# REF-IN-BLE-NS_4-2.net
KiCad netlist of a schematic drawn in EAGLE
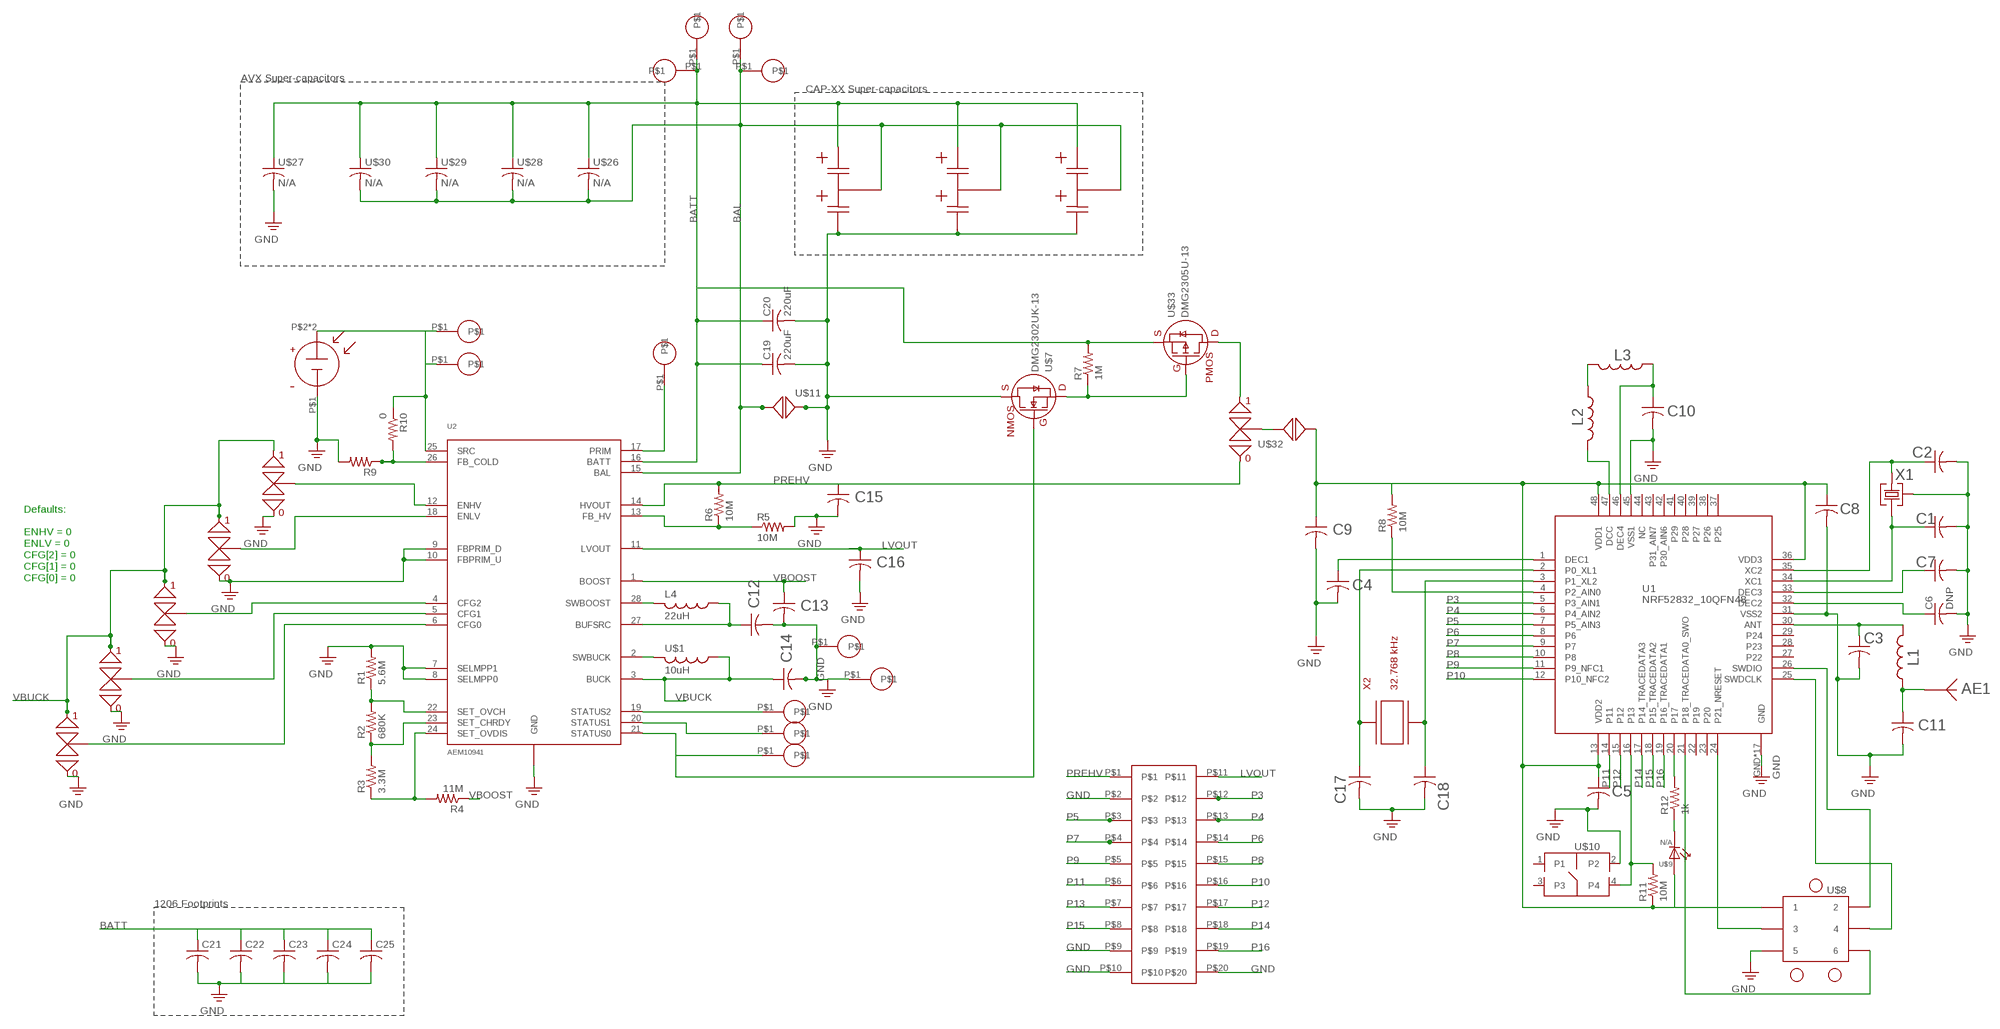
[diagram p0: schematic, sheet 1]

(export (version "E")
  (design (tool "Eeschema 10.0.6"))
  (components
    (comp (ref "AE1")
      (value "2.4GHZ_ANTENNAFLIPPED")
      (footprint "eagle-import:BLE_ANTENNA_NORDIC_FLIPPED")
      (libsource (lib "eagle-import") (part "2.4GHZ_ANTENNAFLIPPED"))
    )
    (comp (ref "C1")
      (value "12pF")
      (footprint "eagle-import:C0603")
      (fields (field (name "MFG_PART#") "C0603C120J5GACTU"))
      (libsource (lib "eagle-import") (part "C-USC0603T-12PF"))
    )
    (comp (ref "C2")
      (value "12pF")
      (footprint "eagle-import:C0603")
      (fields (field (name "MFG_PART#") "C0603C120J5GACTU"))
      (libsource (lib "eagle-import") (part "C-USC0603T-12PF"))
    )
    (comp (ref "C3")
      (value "0.8pF")
      (footprint "eagle-import:C0603")
      (fields (field (name "MFG_PART#") "CBR06C808B5GAC "))
      (libsource (lib "eagle-import") (part "C-USC0603T-0.8PF"))
    )
    (comp (ref "C4")
      (value "100nF")
      (footprint "eagle-import:C0603")
      (fields (field (name "MFG_PART#") "CL10B104KB8NNNC"))
      (libsource (lib "eagle-import") (part "C-USC0603T-100NF"))
    )
    (comp (ref "C5")
      (value "100nF")
      (footprint "eagle-import:C0603")
      (fields (field (name "MFG_PART#") "CL10B104KB8NNNC"))
      (libsource (lib "eagle-import") (part "C-USC0603T-100NF"))
    )
    (comp (ref "C6")
      (value "DNP")
      (footprint "eagle-import:C0603")
      (libsource (lib "eagle-import") (part "C-USC0603"))
    )
    (comp (ref "C7")
      (value "100pF")
      (footprint "eagle-import:C0603")
      (fields (field (name "MFG_PART#") "CL10C101JB8NNNC"))
      (libsource (lib "eagle-import") (part "C-USC0603T-100PF"))
    )
    (comp (ref "C8")
      (value "100nF")
      (footprint "eagle-import:C0603")
      (fields (field (name "MFG_PART#") "CL10B104KB8NNNC"))
      (libsource (lib "eagle-import") (part "C-USC0603T-100NF"))
    )
    (comp (ref "C9")
      (value "4.7uF")
      (footprint "eagle-import:C0603")
      (fields (field (name "MFG_PART#") "CL10A475KQ8NNWC "))
      (libsource (lib "eagle-import") (part "C-USC0603T-4.7UF"))
    )
    (comp (ref "C10")
      (value "1uF")
      (footprint "eagle-import:C0603")
      (fields (field (name "MFG_PART#") "CL10A105KP8NNNC ") (field (name "PERCENTAGE") "10%"))
      (libsource (lib "eagle-import") (part "C-USC0603T-1UF"))
    )
    (comp (ref "C11")
      (value "DNP")
      (footprint "eagle-import:C0603")
      (libsource (lib "eagle-import") (part "C-USC0603"))
    )
    (comp (ref "C12")
      (value "10uF")
      (footprint "eagle-import:C0603")
      (fields (field (name "MFG_PART#") "GRM188R61E106MA73D"))
      (libsource (lib "eagle-import") (part "C-USC0603T-10UF"))
    )
    (comp (ref "C13")
      (value "22uF")
      (footprint "eagle-import:C0603")
      (fields (field (name "MFG_PART#") "GRM188R61A226ME15D"))
      (libsource (lib "eagle-import") (part "C-USC0603T-22UF"))
    )
    (comp (ref "C14")
      (value "10uF")
      (footprint "eagle-import:C0603")
      (fields (field (name "MFG_PART#") "GRM188R61E106MA73D"))
      (libsource (lib "eagle-import") (part "C-USC0603T-10UF"))
    )
    (comp (ref "C15")
      (value "10uF")
      (footprint "eagle-import:C0603")
      (fields (field (name "MFG_PART#") "GRM188R61E106MA73D"))
      (libsource (lib "eagle-import") (part "C-USC0603T-10UF"))
    )
    (comp (ref "C16")
      (value "10uF")
      (footprint "eagle-import:C0603")
      (fields (field (name "MFG_PART#") "GRM188R61E106MA73D"))
      (libsource (lib "eagle-import") (part "C-USC0603T-10UF"))
    )
    (comp (ref "C17")
      (value "12pF")
      (footprint "eagle-import:C0603")
      (fields (field (name "MFG_PART#") "C0603C120J5GACTU"))
      (libsource (lib "eagle-import") (part "C-USC0603T-12PF"))
    )
    (comp (ref "C18")
      (value "12pF")
      (footprint "eagle-import:C0603")
      (fields (field (name "MFG_PART#") "C0603C120J5GACTU"))
      (libsource (lib "eagle-import") (part "C-USC0603T-12PF"))
    )
    (comp (ref "C19")
      (value "220uF")
      (footprint "eagle-import:C1206")
      (fields (field (name "MFG_PART#") "GRM31CC80G227ME11L"))
      (libsource (lib "eagle-import") (part "C-USC1206T-220UF"))
    )
    (comp (ref "C20")
      (value "220uF")
      (footprint "eagle-import:C1206")
      (fields (field (name "MFG_PART#") "GRM31CC80G227ME11L"))
      (libsource (lib "eagle-import") (part "C-USC1206T-220UF"))
    )
    (comp (ref "C21")
      (value "C-USC1206")
      (footprint "eagle-import:C1206")
      (libsource (lib "eagle-import") (part "C-USC1206"))
    )
    (comp (ref "C22")
      (value "C-USC1206")
      (footprint "eagle-import:C1206")
      (libsource (lib "eagle-import") (part "C-USC1206"))
    )
    (comp (ref "C23")
      (value "C-USC1206")
      (footprint "eagle-import:C1206")
      (libsource (lib "eagle-import") (part "C-USC1206"))
    )
    (comp (ref "C24")
      (value "C-USC1206")
      (footprint "eagle-import:C1206")
      (libsource (lib "eagle-import") (part "C-USC1206"))
    )
    (comp (ref "C25")
      (value "C-USC1206")
      (footprint "eagle-import:C1206")
      (libsource (lib "eagle-import") (part "C-USC1206"))
    )
    (comp (ref "L1")
      (value "3.9nH")
      (footprint "eagle-import:L0603")
      (fields (field (name "MFG_PART#") "L-14C3N9SV4T "))
      (libsource (lib "eagle-import") (part "L0603V-3.9NH"))
    )
    (comp (ref "L2")
      (value "10uH")
      (footprint "eagle-import:L0603")
      (fields (field (name "MFG_PART#") "LBR2012T100M"))
      (libsource (lib "eagle-import") (part "L0603V-10UH"))
    )
    (comp (ref "L3")
      (value "15nH")
      (footprint "eagle-import:L0603")
      (fields (field (name "MFG_PART#") "L-14C15NJV4T"))
      (libsource (lib "eagle-import") (part "L0603V-15NH"))
    )
    (comp (ref "L4")
      (value "22uH")
      (footprint "eagle-import:744031220")
      (fields (field (name "MFG_PART#") "744031220"))
      (libsource (lib "eagle-import") (part "744031220"))
    )
    (comp (ref "R1")
      (value "5.6M")
      (footprint "eagle-import:R0603")
      (libsource (lib "eagle-import") (part "R-US_R0603"))
    )
    (comp (ref "R2")
      (value "680K")
      (footprint "eagle-import:R0603")
      (libsource (lib "eagle-import") (part "R-US_R0603"))
    )
    (comp (ref "R3")
      (value "3.3M")
      (footprint "eagle-import:R0603")
      (libsource (lib "eagle-import") (part "R-US_R0603"))
    )
    (comp (ref "R4")
      (value "11M")
      (footprint "eagle-import:R0603")
      (libsource (lib "eagle-import") (part "R-US_R0603"))
    )
    (comp (ref "R5")
      (value "10M")
      (footprint "eagle-import:R0603")
      (libsource (lib "eagle-import") (part "R-US_R0603"))
    )
    (comp (ref "R6")
      (value "10M")
      (footprint "eagle-import:R0603")
      (libsource (lib "eagle-import") (part "R-US_R0603"))
    )
    (comp (ref "R7")
      (value "1M")
      (footprint "eagle-import:R0603")
      (libsource (lib "eagle-import") (part "R-US_R0603"))
    )
    (comp (ref "R8")
      (value "10M")
      (footprint "eagle-import:R0603")
      (libsource (lib "eagle-import") (part "R-US_R0603"))
    )
    (comp (ref "R9")
      (value "R-US_R0603")
      (footprint "eagle-import:R0603")
      (libsource (lib "eagle-import") (part "R-US_R0603"))
    )
    (comp (ref "R10")
      (value "0")
      (footprint "eagle-import:R0603")
      (libsource (lib "eagle-import") (part "R-US_R0603"))
    )
    (comp (ref "R11")
      (value "10M")
      (footprint "eagle-import:R0603")
      (libsource (lib "eagle-import") (part "R-US_R0603"))
    )
    (comp (ref "R12")
      (value "1k")
      (footprint "eagle-import:R0603")
      (libsource (lib "eagle-import") (part "R-US_R0603"))
    )
    (comp (ref "U$1")
      (value "10uH")
      (footprint "eagle-import:L0603")
      (fields (field (name "MFG_PART#") "LBR2012T100M"))
      (libsource (lib "eagle-import") (part "L0603V-10UH"))
    )
    (comp (ref "U$2")
      (value "N/A")
      (footprint "eagle-import:DOUBLE_SOLDER_BRIDGE_0_CLOSED")
      (libsource (lib "eagle-import") (part "DOUBLE_SOLDER_BRIDGE0_CLOSED"))
    )
    (comp (ref "U$3")
      (value "N/A")
      (footprint "eagle-import:DOUBLE_SOLDER_BRIDGE_0_CLOSED")
      (libsource (lib "eagle-import") (part "DOUBLE_SOLDER_BRIDGE0_CLOSED"))
    )
    (comp (ref "U$4")
      (value "N/A")
      (footprint "eagle-import:DOUBLE_SOLDER_BRIDGE_0_CLOSED")
      (libsource (lib "eagle-import") (part "DOUBLE_SOLDER_BRIDGE0_CLOSED"))
    )
    (comp (ref "U$5")
      (value "N/A")
      (footprint "eagle-import:DOUBLE_SOLDER_BRIDGE_0_CLOSED")
      (libsource (lib "eagle-import") (part "DOUBLE_SOLDER_BRIDGE0_CLOSED"))
    )
    (comp (ref "U$6")
      (value "N/A")
      (footprint "eagle-import:DOUBLE_SOLDER_BRIDGE_0_CLOSED")
      (libsource (lib "eagle-import") (part "DOUBLE_SOLDER_BRIDGE0_CLOSED"))
    )
    (comp (ref "U$7")
      (value "DMG2302UK-13")
      (footprint "eagle-import:SOT-23-3-DIODESINC")
      (libsource (lib "eagle-import") (part "DMG2302UK-13"))
    )
    (comp (ref "U$8")
      (value "N/A")
      (footprint "eagle-import:TC2030-IDC")
      (libsource (lib "eagle-import") (part "TC2030-IDC"))
    )
    (comp (ref "U$9")
      (value "N/A")
      (footprint "eagle-import:APT1608LZGCK")
      (fields (field (name "MFG_PART#") "APT1608LZGCK"))
      (libsource (lib "eagle-import") (part "APT1608LZGCK"))
    )
    (comp (ref "U$10")
      (value "MJTP1140")
      (footprint "eagle-import:MJTP1140A")
      (fields (field (name "MFG_PART#") "TL3315NF100Q "))
      (libsource (lib "eagle-import") (part "MJTP1140"))
    )
    (comp (ref "U$11")
      (value "SOLDER_BRIGDECLOSED")
      (footprint "eagle-import:SOLDER_BRIDGE_CLOSED")
      (libsource (lib "eagle-import") (part "SOLDER_BRIGDECLOSED"))
    )
    (comp (ref "U$12")
      (value "N/A")
      (footprint "eagle-import:1MM_PAD")
      (libsource (lib "eagle-import") (part "1MM_PAD"))
    )
    (comp (ref "U$13")
      (value "N/A")
      (footprint "eagle-import:1MM_PAD")
      (libsource (lib "eagle-import") (part "1MM_PAD"))
    )
    (comp (ref "U$14")
      (value "N/A")
      (footprint "eagle-import:1MM_PAD")
      (libsource (lib "eagle-import") (part "1MM_PAD"))
    )
    (comp (ref "U$15")
      (value "N/A")
      (footprint "eagle-import:1MM_PAD")
      (libsource (lib "eagle-import") (part "1MM_PAD"))
    )
    (comp (ref "U$16")
      (value "N/A")
      (footprint "eagle-import:SOLAR_CELL_37X54MM")
      (libsource (lib "eagle-import") (part "SOLAR_CELL_LL200_2.4_37"))
    )
    (comp (ref "U$17")
      (value "N/A")
      (footprint "eagle-import:1MM_PAD")
      (libsource (lib "eagle-import") (part "1MM_PAD"))
    )
    (comp (ref "U$18")
      (value "N/A")
      (footprint "eagle-import:1MM_PAD")
      (libsource (lib "eagle-import") (part "1MM_PAD"))
    )
    (comp (ref "U$19")
      (value "N/A")
      (footprint "eagle-import:1MM_PAD")
      (libsource (lib "eagle-import") (part "1MM_PAD"))
    )
    (comp (ref "U$20")
      (value "20PIN_CONN")
      (footprint "eagle-import:20PIN_CONN")
      (libsource (lib "eagle-import") (part "20PIN_CONN"))
    )
    (comp (ref "U$23")
      (value "N/A")
      (footprint "eagle-import:CAP-XX_A-TYPE")
      (libsource (lib "eagle-import") (part "CAP-XX_A-TYPE"))
    )
    (comp (ref "U$24")
      (value "N/A")
      (footprint "eagle-import:CAP-XX_S-TYPE")
      (libsource (lib "eagle-import") (part "CAP-XX_S-TYPE"))
    )
    (comp (ref "U$25")
      (value "N/A")
      (footprint "eagle-import:CAP-XX_W-TYPE")
      (libsource (lib "eagle-import") (part "CAP-XX_W-TYPE"))
    )
    (comp (ref "U$26")
      (value "N/A")
      (footprint "eagle-import:BZ01_L-TYPE")
      (libsource (lib "eagle-import") (part "BZ01_L-TYPE"))
    )
    (comp (ref "U$27")
      (value "N/A")
      (footprint "eagle-import:BZ059_N-TYPE")
      (libsource (lib "eagle-import") (part "BZ059_N-TYPE"))
    )
    (comp (ref "U$28")
      (value "N/A")
      (footprint "eagle-import:BZ01_S-TYPE")
      (libsource (lib "eagle-import") (part "BZ01_S-TYPE"))
    )
    (comp (ref "U$29")
      (value "N/A")
      (footprint "eagle-import:BZ05_S-TYPE")
      (libsource (lib "eagle-import") (part "BZ05_S-TYPE"))
    )
    (comp (ref "U$30")
      (value "N/A")
      (footprint "eagle-import:BZ09_S-TYPE")
      (libsource (lib "eagle-import") (part "BZ09_S-TYPE"))
    )
    (comp (ref "U$31")
      (value "DOUBLE_SOLDER_BRIDGE1_CLOSED")
      (footprint "eagle-import:DOUBLE_SOLDER_BRIDGE_1_CLOSED")
      (libsource (lib "eagle-import") (part "DOUBLE_SOLDER_BRIDGE1_CLOSED"))
    )
    (comp (ref "U$32")
      (value "SOLDER_BRIGDECLOSED")
      (footprint "eagle-import:SOLDER_BRIDGE_CLOSED")
      (libsource (lib "eagle-import") (part "SOLDER_BRIGDECLOSED"))
    )
    (comp (ref "U$33")
      (value "DMG2305U-13")
      (footprint "eagle-import:SOT-23-3-DIODESINC")
      (libsource (lib "eagle-import") (part "DMG2305U-13"))
    )
    (comp (ref "U$35")
      (value "N/A")
      (footprint "eagle-import:1MM_PAD")
      (libsource (lib "eagle-import") (part "1MM_PAD"))
    )
    (comp (ref "U$36")
      (value "N/A")
      (footprint "eagle-import:1MM_PAD")
      (libsource (lib "eagle-import") (part "1MM_PAD"))
    )
    (comp (ref "U$39")
      (value "N/A")
      (footprint "eagle-import:1MM_PAD")
      (libsource (lib "eagle-import") (part "1MM_PAD"))
    )
    (comp (ref "U$40")
      (value "N/A")
      (footprint "eagle-import:1MM_PAD")
      (libsource (lib "eagle-import") (part "1MM_PAD"))
    )
    (comp (ref "U$41")
      (value "N/A")
      (footprint "eagle-import:1MM_PAD")
      (libsource (lib "eagle-import") (part "1MM_PAD"))
    )
    (comp (ref "U1")
      (value "NRF52832_10QFN48")
      (footprint "eagle-import:NRF52832_10")
      (fields (field (name "MFG_PART#") "NRF52832-QFAA-R"))
      (libsource (lib "eagle-import") (part "NRF52832_10QFN48"))
    )
    (comp (ref "U2")
      (value "AEM10941")
      (footprint "eagle-import:QFN28_5X5_05PITCH")
      (fields (field (name "MFG_PART#") "AEM10941-QFN "))
      (libsource (lib "eagle-import") (part "AEM10941"))
    )
    (comp (ref "X1")
      (value "32 MHz")
      (footprint "eagle-import:FA-128-EPSON")
      (fields (field (name "MFG_PART#") "FA-128 32.0000MF10Z-AJ3"))
      (libsource (lib "eagle-import") (part "FA-128-32MHZMF10Z-AJ5"))
    )
    (comp (ref "X2")
      (value "32.768 kHz")
      (footprint "eagle-import:FC-135")
      (fields (field (name "MFG_PART#") "FC-135 32.7680KA-AC"))
      (libsource (lib "eagle-import") (part "FC-135_32.7680KA-AC"))
    )
  )
  (nets
    (net (code "1") (name "/BAL") (class "Default")
      (node (ref "U$11") (pin "P$1") (pinfunction "P1_P$1") (pintype "bidirectional"))
      (node (ref "U$19") (pin "P$1") (pinfunction "P$1_P$1") (pintype "bidirectional"))
      (node (ref "U$23") (pin "P$1") (pinfunction "BAL_P$1") (pintype "bidirectional"))
      (node (ref "U$24") (pin "P$1") (pinfunction "BAL_P$1") (pintype "bidirectional"))
      (node (ref "U$25") (pin "P$1") (pinfunction "BAL_P$1") (pintype "bidirectional"))
      (node (ref "U$26") (pin "P$3") (pinfunction "2_P$3") (pintype "passive"))
      (node (ref "U$26") (pin "P$4") (pinfunction "2_P$4") (pintype "passive"))
      (node (ref "U$28") (pin "P$3") (pinfunction "2_P$3") (pintype "passive"))
      (node (ref "U$29") (pin "P$3") (pinfunction "2_P$3") (pintype "passive"))
      (node (ref "U$30") (pin "P$3") (pinfunction "2_P$3") (pintype "passive"))
      (node (ref "U$41") (pin "P$1") (pinfunction "P$1_P$1") (pintype "bidirectional"))
      (node (ref "U2") (pin "15") (pinfunction "BAL_15") (pintype "bidirectional"))
    )
    (net (code "2") (name "/BATT") (class "Default")
      (node (ref "C19") (pin "1") (pinfunction "1_1") (pintype "passive"))
      (node (ref "C20") (pin "1") (pinfunction "1_1") (pintype "passive"))
      (node (ref "C21") (pin "1") (pinfunction "1_1") (pintype "passive"))
      (node (ref "C22") (pin "1") (pinfunction "1_1") (pintype "passive"))
      (node (ref "C23") (pin "1") (pinfunction "1_1") (pintype "passive"))
      (node (ref "C24") (pin "1") (pinfunction "1_1") (pintype "passive"))
      (node (ref "C25") (pin "1") (pinfunction "1_1") (pintype "passive"))
      (node (ref "R7") (pin "2") (pinfunction "2_2") (pintype "passive"))
      (node (ref "U$18") (pin "P$1") (pinfunction "P$1_P$1") (pintype "bidirectional"))
      (node (ref "U$23") (pin "P$2") (pinfunction "+_P$2") (pintype "bidirectional"))
      (node (ref "U$24") (pin "P$2") (pinfunction "+_P$2") (pintype "bidirectional"))
      (node (ref "U$25") (pin "P$2") (pinfunction "+_P$2") (pintype "bidirectional"))
      (node (ref "U$26") (pin "P$1") (pinfunction "1_P$1") (pintype "passive"))
      (node (ref "U$26") (pin "P$2") (pinfunction "1_P$2") (pintype "passive"))
      (node (ref "U$27") (pin "P$1") (pinfunction "1_P$1") (pintype "passive"))
      (node (ref "U$28") (pin "P$1") (pinfunction "1_P$1") (pintype "passive"))
      (node (ref "U$28") (pin "P$2") (pinfunction "1_P$2") (pintype "passive"))
      (node (ref "U$29") (pin "P$1") (pinfunction "1_P$1") (pintype "passive"))
      (node (ref "U$29") (pin "P$2") (pinfunction "1_P$2") (pintype "passive"))
      (node (ref "U$30") (pin "P$1") (pinfunction "1_P$1") (pintype "passive"))
      (node (ref "U$30") (pin "P$2") (pinfunction "1_P$2") (pintype "passive"))
      (node (ref "U$33") (pin "2") (pinfunction "S_2") (pintype "bidirectional"))
      (node (ref "U$40") (pin "P$1") (pinfunction "P$1_P$1") (pintype "bidirectional"))
      (node (ref "U2") (pin "16") (pinfunction "BATT_16") (pintype "bidirectional"))
    )
    (net (code "3") (name "/LVOUT") (class "Default")
      (node (ref "C16") (pin "1") (pinfunction "1_1") (pintype "passive"))
      (node (ref "U$20") (pin "P$11") (pinfunction "P$11_P$11") (pintype "bidirectional"))
      (node (ref "U2") (pin "11") (pinfunction "LVOUT_11") (pintype "output"))
    )
    (net (code "4") (name "/P3") (class "Default")
      (node (ref "U$20") (pin "P$12") (pinfunction "P$12_P$12") (pintype "bidirectional"))
      (node (ref "U1") (pin "5") (pinfunction "P3_AIN1_5") (pintype "bidirectional"))
    )
    (net (code "5") (name "/P4") (class "Default")
      (node (ref "U$20") (pin "P$13") (pinfunction "P$13_P$13") (pintype "bidirectional"))
      (node (ref "U1") (pin "6") (pinfunction "P4_AIN2_6") (pintype "bidirectional"))
    )
    (net (code "6") (name "/P5") (class "Default")
      (node (ref "U$20") (pin "P$3") (pinfunction "P$3_P$3") (pintype "bidirectional"))
      (node (ref "U1") (pin "7") (pinfunction "P5_AIN3_7") (pintype "bidirectional"))
    )
    (net (code "7") (name "/P6") (class "Default")
      (node (ref "U$20") (pin "P$14") (pinfunction "P$14_P$14") (pintype "bidirectional"))
      (node (ref "U1") (pin "8") (pinfunction "P6_8") (pintype "bidirectional"))
    )
    (net (code "8") (name "/P7") (class "Default")
      (node (ref "U$20") (pin "P$4") (pinfunction "P$4_P$4") (pintype "bidirectional"))
      (node (ref "U1") (pin "9") (pinfunction "P7_9") (pintype "bidirectional"))
    )
    (net (code "9") (name "/P8") (class "Default")
      (node (ref "U$20") (pin "P$15") (pinfunction "P$15_P$15") (pintype "bidirectional"))
      (node (ref "U1") (pin "10") (pinfunction "P8_10") (pintype "bidirectional"))
    )
    (net (code "10") (name "/P9") (class "Default")
      (node (ref "U$20") (pin "P$5") (pinfunction "P$5_P$5") (pintype "bidirectional"))
      (node (ref "U1") (pin "11") (pinfunction "P9_NFC1_11") (pintype "bidirectional"))
    )
    (net (code "11") (name "/P10") (class "Default")
      (node (ref "U$20") (pin "P$16") (pinfunction "P$16_P$16") (pintype "bidirectional"))
      (node (ref "U1") (pin "12") (pinfunction "P10_NFC2_12") (pintype "bidirectional"))
    )
    (net (code "12") (name "/P11") (class "Default")
      (node (ref "U$20") (pin "P$6") (pinfunction "P$6_P$6") (pintype "bidirectional"))
      (node (ref "U1") (pin "14") (pinfunction "P11_14") (pintype "bidirectional"))
    )
    (net (code "13") (name "/P12") (class "Default")
      (node (ref "U$20") (pin "P$17") (pinfunction "P$17_P$17") (pintype "bidirectional"))
      (node (ref "U1") (pin "15") (pinfunction "P12_15") (pintype "bidirectional"))
    )
    (net (code "14") (name "/P13") (class "Default")
      (node (ref "U$20") (pin "P$7") (pinfunction "P$7_P$7") (pintype "bidirectional"))
    )
    (net (code "15") (name "/P14") (class "Default")
      (node (ref "U$20") (pin "P$18") (pinfunction "P$18_P$18") (pintype "bidirectional"))
      (node (ref "U1") (pin "17") (pinfunction "P14_TRACEDATA3_17") (pintype "bidirectional"))
    )
    (net (code "16") (name "/P15") (class "Default")
      (node (ref "U$20") (pin "P$8") (pinfunction "P$8_P$8") (pintype "bidirectional"))
      (node (ref "U1") (pin "18") (pinfunction "P15_TRACEDATA2_18") (pintype "bidirectional"))
    )
    (net (code "17") (name "/P16") (class "Default")
      (node (ref "U$20") (pin "P$19") (pinfunction "P$19_P$19") (pintype "bidirectional"))
      (node (ref "U1") (pin "19") (pinfunction "P16_TRACEDATA1_19") (pintype "bidirectional"))
    )
    (net (code "18") (name "/PREHV") (class "Default")
      (node (ref "C15") (pin "1") (pinfunction "1_1") (pintype "passive"))
      (node (ref "R6") (pin "2") (pinfunction "2_2") (pintype "passive"))
      (node (ref "U$20") (pin "P$1") (pinfunction "P$1_P$1") (pintype "bidirectional"))
      (node (ref "U$31") (pin "IN0") (pinfunction "IN0_IN0") (pintype "bidirectional"))
      (node (ref "U2") (pin "14") (pinfunction "HVOUT_14") (pintype "output"))
    )
    (net (code "19") (name "/VBOOST") (class "Default")
      (node (ref "C13") (pin "1") (pinfunction "1_1") (pintype "passive"))
      (node (ref "R4") (pin "1") (pinfunction "1_1") (pintype "passive"))
      (node (ref "U2") (pin "1") (pinfunction "BOOST_1") (pintype "bidirectional"))
    )
    (net (code "20") (name "/VBUCK") (class "Default")
      (node (ref "C14") (pin "1") (pinfunction "1_1") (pintype "passive"))
      (node (ref "U$1") (pin "1") (pinfunction "1_1") (pintype "passive"))
      (node (ref "U$2") (pin "IN1") (pinfunction "IN1_IN1") (pintype "bidirectional"))
      (node (ref "U$3") (pin "IN1") (pinfunction "IN1_IN1") (pintype "bidirectional"))
      (node (ref "U$4") (pin "IN1") (pinfunction "IN1_IN1") (pintype "bidirectional"))
      (node (ref "U$5") (pin "IN1") (pinfunction "IN1_IN1") (pintype "bidirectional"))
      (node (ref "U$6") (pin "IN1") (pinfunction "IN1_IN1") (pintype "bidirectional"))
      (node (ref "U2") (pin "3") (pinfunction "BUCK_3") (pintype "bidirectional"))
    )
    (net (code "21") (name "GND") (class "Default")
      (node (ref "C1") (pin "2") (pinfunction "2_2") (pintype "passive"))
      (node (ref "C10") (pin "2") (pinfunction "2_2") (pintype "passive"))
      (node (ref "C11") (pin "2") (pinfunction "2_2") (pintype "passive"))
      (node (ref "C12") (pin "2") (pinfunction "2_2") (pintype "passive"))
      (node (ref "C13") (pin "2") (pinfunction "2_2") (pintype "passive"))
      (node (ref "C14") (pin "2") (pinfunction "2_2") (pintype "passive"))
      (node (ref "C15") (pin "2") (pinfunction "2_2") (pintype "passive"))
      (node (ref "C16") (pin "2") (pinfunction "2_2") (pintype "passive"))
      (node (ref "C17") (pin "2") (pinfunction "2_2") (pintype "passive"))
      (node (ref "C18") (pin "2") (pinfunction "2_2") (pintype "passive"))
      (node (ref "C19") (pin "2") (pinfunction "2_2") (pintype "passive"))
      (node (ref "C2") (pin "2") (pinfunction "2_2") (pintype "passive"))
      (node (ref "C20") (pin "2") (pinfunction "2_2") (pintype "passive"))
      (node (ref "C21") (pin "2") (pinfunction "2_2") (pintype "passive"))
      (node (ref "C22") (pin "2") (pinfunction "2_2") (pintype "passive"))
      (node (ref "C23") (pin "2") (pinfunction "2_2") (pintype "passive"))
      (node (ref "C24") (pin "2") (pinfunction "2_2") (pintype "passive"))
      (node (ref "C25") (pin "2") (pinfunction "2_2") (pintype "passive"))
      (node (ref "C3") (pin "2") (pinfunction "2_2") (pintype "passive"))
      (node (ref "C4") (pin "2") (pinfunction "2_2") (pintype "passive"))
      (node (ref "C5") (pin "2") (pinfunction "2_2") (pintype "passive"))
      (node (ref "C6") (pin "2") (pinfunction "2_2") (pintype "passive"))
      (node (ref "C7") (pin "2") (pinfunction "2_2") (pintype "passive"))
      (node (ref "C8") (pin "2") (pinfunction "2_2") (pintype "passive"))
      (node (ref "C9") (pin "2") (pinfunction "2_2") (pintype "passive"))
      (node (ref "R1") (pin "2") (pinfunction "2_2") (pintype "passive"))
      (node (ref "R5") (pin "2") (pinfunction "2_2") (pintype "passive"))
      (node (ref "R9") (pin "2") (pinfunction "2_2") (pintype "passive"))
      (node (ref "U$10") (pin "2") (pinfunction "P2_2") (pintype "bidirectional"))
      (node (ref "U$11") (pin "P$2") (pinfunction "P2_P$2") (pintype "bidirectional"))
      (node (ref "U$16") (pin "P$1") (pinfunction "GND_P$1") (pintype "bidirectional"))
      (node (ref "U$17") (pin "P$1") (pinfunction "P$1_P$1") (pintype "bidirectional"))
      (node (ref "U$2") (pin "IN0") (pinfunction "IN0_IN0") (pintype "bidirectional"))
      (node (ref "U$20") (pin "P$10") (pinfunction "P$10_P$10") (pintype "bidirectional"))
      (node (ref "U$20") (pin "P$2") (pinfunction "P$2_P$2") (pintype "bidirectional"))
      (node (ref "U$20") (pin "P$20") (pinfunction "P$20_P$20") (pintype "bidirectional"))
      (node (ref "U$20") (pin "P$9") (pinfunction "P$9_P$9") (pintype "bidirectional"))
      (node (ref "U$23") (pin "P$3") (pinfunction "-_P$3") (pintype "bidirectional"))
      (node (ref "U$24") (pin "P$3") (pinfunction "-_P$3") (pintype "bidirectional"))
      (node (ref "U$25") (pin "P$3") (pinfunction "-_P$3") (pintype "bidirectional"))
      (node (ref "U$27") (pin "P$2") (pinfunction "2_P$2") (pintype "passive"))
      (node (ref "U$3") (pin "IN0") (pinfunction "IN0_IN0") (pintype "bidirectional"))
      (node (ref "U$35") (pin "P$1") (pinfunction "P$1_P$1") (pintype "bidirectional"))
      (node (ref "U$4") (pin "IN0") (pinfunction "IN0_IN0") (pintype "bidirectional"))
      (node (ref "U$5") (pin "IN0") (pinfunction "IN0_IN0") (pintype "bidirectional"))
      (node (ref "U$6") (pin "IN0") (pinfunction "IN0_IN0") (pintype "bidirectional"))
      (node (ref "U$7") (pin "2") (pinfunction "S_2") (pintype "bidirectional"))
      (node (ref "U$8") (pin "P5") (pinfunction "5_P5") (pintype "bidirectional"))
      (node (ref "U1") (pin "31") (pinfunction "VSS2_31") (pintype "bidirectional"))
      (node (ref "U1") (pin "45") (pinfunction "VSS1_45") (pintype "bidirectional"))
      (node (ref "U1") (pin "GND") (pinfunction "GND_GND") (pintype "bidirectional"))
      (node (ref "U1") (pin "P$10") (pinfunction "GND_P$10") (pintype "bidirectional"))
      (node (ref "U1") (pin "P$11") (pinfunction "GND_P$11") (pintype "bidirectional"))
      (node (ref "U1") (pin "P$12") (pinfunction "GND_P$12") (pintype "bidirectional"))
      (node (ref "U1") (pin "P$13") (pinfunction "GND_P$13") (pintype "bidirectional"))
      (node (ref "U1") (pin "P$14") (pinfunction "GND_P$14") (pintype "bidirectional"))
      (node (ref "U1") (pin "P$15") (pinfunction "GND_P$15") (pintype "bidirectional"))
      (node (ref "U1") (pin "P$16") (pinfunction "GND_P$16") (pintype "bidirectional"))
      (node (ref "U1") (pin "P$17") (pinfunction "GND_P$17") (pintype "bidirectional"))
      (node (ref "U1") (pin "P$2") (pinfunction "GND_P$2") (pintype "bidirectional"))
      (node (ref "U1") (pin "P$3") (pinfunction "GND_P$3") (pintype "bidirectional"))
      (node (ref "U1") (pin "P$4") (pinfunction "GND_P$4") (pintype "bidirectional"))
      (node (ref "U1") (pin "P$5") (pinfunction "GND_P$5") (pintype "bidirectional"))
      (node (ref "U1") (pin "P$6") (pinfunction "GND_P$6") (pintype "bidirectional"))
      (node (ref "U1") (pin "P$7") (pinfunction "GND_P$7") (pintype "bidirectional"))
      (node (ref "U1") (pin "P$8") (pinfunction "GND_P$8") (pintype "bidirectional"))
      (node (ref "U1") (pin "P$9") (pinfunction "GND_P$9") (pintype "bidirectional"))
      (node (ref "U2") (pin "10") (pinfunction "FBPRIM_U_10") (pintype "bidirectional"))
      (node (ref "U2") (pin "7") (pinfunction "SELMPP1_7") (pintype "input"))
      (node (ref "U2") (pin "8") (pinfunction "SELMPP0_8") (pintype "input"))
      (node (ref "U2") (pin "9") (pinfunction "FBPRIM_D_9") (pintype "bidirectional"))
      (node (ref "U2") (pin "GND") (pinfunction "GND_GND") (pintype "power_in"))
      (node (ref "U2") (pin "GND1") (pinfunction "GND_GND1") (pintype "power_in"))
      (node (ref "U2") (pin "GND2") (pinfunction "GND_GND2") (pintype "power_in"))
      (node (ref "U2") (pin "GND3") (pinfunction "GND_GND3") (pintype "power_in"))
      (node (ref "U2") (pin "GND4") (pinfunction "GND_GND4") (pintype "power_in"))
      (node (ref "U2") (pin "GND5") (pinfunction "GND_GND5") (pintype "power_in"))
      (node (ref "X1") (pin "P2") (pinfunction "P3_P2") (pintype "bidirectional"))
      (node (ref "X1") (pin "P4") (pinfunction "P3_P4") (pintype "bidirectional"))
    )
    (net (code "22") (name "Net-(AE1-PadP$1)") (class "Default")
      (node (ref "AE1") (pin "P$1") (pinfunction "P$1_P$1") (pintype "bidirectional"))
      (node (ref "C11") (pin "1") (pinfunction "1_1") (pintype "passive"))
      (node (ref "L1") (pin "1") (pinfunction "1_1") (pintype "passive"))
    )
    (net (code "23") (name "Net-(L2-Pad1)") (class "Default")
      (node (ref "L2") (pin "1") (pinfunction "1_1") (pintype "passive"))
      (node (ref "L3") (pin "2") (pinfunction "2_2") (pintype "passive"))
    )
    (net (code "24") (name "Net-(L4-1)") (class "Default")
      (node (ref "C12") (pin "1") (pinfunction "1_1") (pintype "passive"))
      (node (ref "L4") (pin "PIN1") (pinfunction "1_PIN1") (pintype "passive"))
      (node (ref "U2") (pin "27") (pinfunction "BUFSRC_27") (pintype "bidirectional"))
    )
    (net (code "25") (name "Net-(L4-2)") (class "Default")
      (node (ref "L4") (pin "PIN2") (pinfunction "2_PIN2") (pintype "passive"))
      (node (ref "U2") (pin "28") (pinfunction "SWBOOST_28") (pintype "bidirectional"))
    )
    (net (code "26") (name "Net-(R12-Pad1)") (class "Default")
      (node (ref "R12") (pin "1") (pinfunction "1_1") (pintype "passive"))
      (node (ref "U$9") (pin "C") (pinfunction "C_C") (pintype "bidirectional"))
    )
    (net (code "27") (name "Net-(U$7-G)") (class "Default")
      (node (ref "U$15") (pin "P$1") (pinfunction "P$1_P$1") (pintype "bidirectional"))
      (node (ref "U$7") (pin "1") (pinfunction "G_1") (pintype "bidirectional"))
      (node (ref "U2") (pin "21") (pinfunction "STATUS0_21") (pintype "output"))
    )
    (net (code "28") (name "Net-(U$8-2)") (class "Default")
      (node (ref "U$8") (pin "P2") (pinfunction "2_P2") (pintype "bidirectional"))
      (node (ref "U1") (pin "26") (pinfunction "SWDIO_26") (pintype "bidirectional"))
    )
    (net (code "29") (name "Net-(U$8-3)") (class "Default")
      (node (ref "U$8") (pin "P3") (pinfunction "3_P3") (pintype "bidirectional"))
      (node (ref "U1") (pin "24") (pinfunction "P21_NRESET_24") (pintype "bidirectional"))
    )
    (net (code "30") (name "Net-(U$8-4)") (class "Default")
      (node (ref "U$8") (pin "P4") (pinfunction "4_P4") (pintype "bidirectional"))
      (node (ref "U1") (pin "25") (pinfunction "SWDCLK_25") (pintype "bidirectional"))
    )
    (net (code "31") (name "Net-(U$8-6)") (class "Default")
      (node (ref "U$8") (pin "P6") (pinfunction "6_P6") (pintype "bidirectional"))
      (node (ref "U1") (pin "21") (pinfunction "P18_TRACEDATA0_SWO_21") (pintype "bidirectional"))
    )
    (net (code "32") (name "Net-(U$10-P4)") (class "Default")
      (node (ref "R11") (pin "2") (pinfunction "2_2") (pintype "passive"))
      (node (ref "U$10") (pin "4") (pinfunction "P4_4") (pintype "bidirectional"))
      (node (ref "U1") (pin "16") (pinfunction "P13_16") (pintype "bidirectional"))
    )
    (net (code "33") (name "Net-(U$32-P1)") (class "Default")
      (node (ref "C5") (pin "1") (pinfunction "1_1") (pintype "passive"))
      (node (ref "C8") (pin "1") (pinfunction "1_1") (pintype "passive"))
      (node (ref "C9") (pin "1") (pinfunction "1_1") (pintype "passive"))
      (node (ref "R11") (pin "1") (pinfunction "1_1") (pintype "passive"))
      (node (ref "R8") (pin "2") (pinfunction "2_2") (pintype "passive"))
      (node (ref "U$32") (pin "P$1") (pinfunction "P1_P$1") (pintype "bidirectional"))
      (node (ref "U$8") (pin "P1") (pinfunction "1_P1") (pintype "bidirectional"))
      (node (ref "U$9") (pin "A") (pinfunction "A_A") (pintype "bidirectional"))
      (node (ref "U1") (pin "13") (pinfunction "VDD2_13") (pintype "bidirectional"))
      (node (ref "U1") (pin "36") (pinfunction "VDD3_36") (pintype "bidirectional"))
      (node (ref "U1") (pin "48") (pinfunction "VDD1_48") (pintype "bidirectional"))
    )
    (net (code "34") (name "Net-(U$32-P2)") (class "Default")
      (node (ref "U$31") (pin "OUT") (pinfunction "OUT_OUT") (pintype "bidirectional"))
      (node (ref "U$32") (pin "P$2") (pinfunction "P2_P$2") (pintype "bidirectional"))
    )
    (net (code "35") (name "Net-(U$33-D)") (class "Default")
      (node (ref "U$31") (pin "IN1") (pinfunction "IN1_IN1") (pintype "bidirectional"))
      (node (ref "U$33") (pin "3") (pinfunction "D_3") (pintype "bidirectional"))
    )
    (net (code "36") (name "Net-(U$33-G)") (class "Default")
      (node (ref "R7") (pin "1") (pinfunction "1_1") (pintype "passive"))
      (node (ref "U$33") (pin "1") (pinfunction "G_1") (pintype "bidirectional"))
      (node (ref "U$7") (pin "3") (pinfunction "D_3") (pintype "bidirectional"))
    )
    (net (code "37") (name "Net-(U1-ANT)") (class "Default")
      (node (ref "C3") (pin "1") (pinfunction "1_1") (pintype "passive"))
      (node (ref "L1") (pin "2") (pinfunction "2_2") (pintype "passive"))
      (node (ref "U1") (pin "30") (pinfunction "ANT_30") (pintype "bidirectional"))
    )
    (net (code "38") (name "Net-(U1-DCC)") (class "Default")
      (node (ref "L2") (pin "2") (pinfunction "2_2") (pintype "passive"))
      (node (ref "U1") (pin "47") (pinfunction "DCC_47") (pintype "bidirectional"))
    )
    (net (code "39") (name "Net-(U1-DEC1)") (class "Default")
      (node (ref "C4") (pin "1") (pinfunction "1_1") (pintype "passive"))
      (node (ref "U1") (pin "1") (pinfunction "DEC1_1") (pintype "bidirectional"))
    )
    (net (code "40") (name "Net-(U1-DEC2)") (class "Default")
      (node (ref "C6") (pin "1") (pinfunction "1_1") (pintype "passive"))
      (node (ref "U1") (pin "32") (pinfunction "DEC2_32") (pintype "bidirectional"))
    )
    (net (code "41") (name "Net-(U1-DEC3)") (class "Default")
      (node (ref "C7") (pin "1") (pinfunction "1_1") (pintype "passive"))
      (node (ref "U1") (pin "33") (pinfunction "DEC3_33") (pintype "bidirectional"))
    )
    (net (code "42") (name "Net-(U1-DEC4)") (class "Default")
      (node (ref "C10") (pin "1") (pinfunction "1_1") (pintype "passive"))
      (node (ref "L3") (pin "1") (pinfunction "1_1") (pintype "passive"))
      (node (ref "U1") (pin "46") (pinfunction "DEC4_46") (pintype "bidirectional"))
    )
    (net (code "43") (name "Net-(U1-P0_XL1)") (class "Default")
      (node (ref "C17") (pin "1") (pinfunction "1_1") (pintype "passive"))
      (node (ref "U1") (pin "2") (pinfunction "P0_XL1_2") (pintype "bidirectional"))
      (node (ref "X2") (pin "P$1") (pinfunction "P$1_P$1") (pintype "bidirectional"))
    )
    (net (code "44") (name "Net-(U1-P1_XL2)") (class "Default")
      (node (ref "C18") (pin "1") (pinfunction "1_1") (pintype "passive"))
      (node (ref "U1") (pin "3") (pinfunction "P1_XL2_3") (pintype "bidirectional"))
      (node (ref "X2") (pin "P$2") (pinfunction "P$2_P$2") (pintype "bidirectional"))
    )
    (net (code "45") (name "Net-(U1-P2_AIN0)") (class "Default")
      (node (ref "R8") (pin "1") (pinfunction "1_1") (pintype "passive"))
      (node (ref "U1") (pin "4") (pinfunction "P2_AIN0_4") (pintype "bidirectional"))
    )
    (net (code "46") (name "Net-(U1-P17)") (class "Default")
      (node (ref "R12") (pin "2") (pinfunction "2_2") (pintype "passive"))
      (node (ref "U1") (pin "20") (pinfunction "P17_20") (pintype "bidirectional"))
    )
    (net (code "47") (name "Net-(U1-XC1)") (class "Default")
      (node (ref "C1") (pin "1") (pinfunction "1_1") (pintype "passive"))
      (node (ref "U1") (pin "34") (pinfunction "XC1_34") (pintype "bidirectional"))
      (node (ref "X1") (pin "P3") (pinfunction "1_P3") (pintype "passive"))
    )
    (net (code "48") (name "Net-(U1-XC2)") (class "Default")
      (node (ref "C2") (pin "1") (pinfunction "1_1") (pintype "passive"))
      (node (ref "U1") (pin "35") (pinfunction "XC2_35") (pintype "bidirectional"))
      (node (ref "X1") (pin "P1") (pinfunction "2_P1") (pintype "passive"))
    )
    (net (code "49") (name "Net-(U2-CFG0)") (class "Default")
      (node (ref "U$6") (pin "OUT") (pinfunction "OUT_OUT") (pintype "bidirectional"))
      (node (ref "U2") (pin "6") (pinfunction "CFG0_6") (pintype "input"))
    )
    (net (code "50") (name "Net-(U2-CFG1)") (class "Default")
      (node (ref "U$5") (pin "OUT") (pinfunction "OUT_OUT") (pintype "bidirectional"))
      (node (ref "U2") (pin "5") (pinfunction "CFG1_5") (pintype "input"))
    )
    (net (code "51") (name "Net-(U2-CFG2)") (class "Default")
      (node (ref "U$4") (pin "OUT") (pinfunction "OUT_OUT") (pintype "bidirectional"))
      (node (ref "U2") (pin "4") (pinfunction "CFG2_4") (pintype "input"))
    )
    (net (code "52") (name "Net-(U2-ENHV)") (class "Default")
      (node (ref "U$2") (pin "OUT") (pinfunction "OUT_OUT") (pintype "bidirectional"))
      (node (ref "U2") (pin "12") (pinfunction "ENHV_12") (pintype "input"))
    )
    (net (code "53") (name "Net-(U2-ENLV)") (class "Default")
      (node (ref "U$3") (pin "OUT") (pinfunction "OUT_OUT") (pintype "bidirectional"))
      (node (ref "U2") (pin "18") (pinfunction "ENLV_18") (pintype "input"))
    )
    (net (code "54") (name "Net-(U2-FB_COLD)") (class "Default")
      (node (ref "R10") (pin "2") (pinfunction "2_2") (pintype "passive"))
      (node (ref "R9") (pin "1") (pinfunction "1_1") (pintype "passive"))
      (node (ref "U2") (pin "26") (pinfunction "FB_COLD_26") (pintype "bidirectional"))
    )
    (net (code "55") (name "Net-(U2-FB_HV)") (class "Default")
      (node (ref "R5") (pin "1") (pinfunction "1_1") (pintype "passive"))
      (node (ref "R6") (pin "1") (pinfunction "1_1") (pintype "passive"))
      (node (ref "U2") (pin "13") (pinfunction "FB_HV_13") (pintype "input"))
    )
    (net (code "56") (name "Net-(U2-PRIM)") (class "Default")
      (node (ref "U$12") (pin "P$1") (pinfunction "P$1_P$1") (pintype "bidirectional"))
      (node (ref "U2") (pin "17") (pinfunction "PRIM_17") (pintype "bidirectional"))
    )
    (net (code "57") (name "Net-(U2-SET_CHRDY)") (class "Default")
      (node (ref "R2") (pin "1") (pinfunction "1_1") (pintype "passive"))
      (node (ref "R3") (pin "2") (pinfunction "2_2") (pintype "passive"))
      (node (ref "U2") (pin "23") (pinfunction "SET_CHRDY_23") (pintype "bidirectional"))
    )
    (net (code "58") (name "Net-(U2-SET_OVCH)") (class "Default")
      (node (ref "R1") (pin "1") (pinfunction "1_1") (pintype "passive"))
      (node (ref "R2") (pin "2") (pinfunction "2_2") (pintype "passive"))
      (node (ref "U2") (pin "22") (pinfunction "SET_OVCH_22") (pintype "bidirectional"))
    )
    (net (code "59") (name "Net-(U2-SET_OVDIS)") (class "Default")
      (node (ref "R3") (pin "1") (pinfunction "1_1") (pintype "passive"))
      (node (ref "R4") (pin "2") (pinfunction "2_2") (pintype "passive"))
      (node (ref "U2") (pin "24") (pinfunction "SET_OVDIS_24") (pintype "bidirectional"))
    )
    (net (code "60") (name "Net-(U2-SRC)") (class "Default")
      (node (ref "R10") (pin "1") (pinfunction "1_1") (pintype "passive"))
      (node (ref "U$16") (pin "P$2") (pinfunction "VOUT_P$2") (pintype "bidirectional"))
      (node (ref "U$16") (pin "P$3") (pinfunction "VOUT_P$3") (pintype "bidirectional"))
      (node (ref "U$36") (pin "P$1") (pinfunction "P$1_P$1") (pintype "bidirectional"))
      (node (ref "U$39") (pin "P$1") (pinfunction "P$1_P$1") (pintype "bidirectional"))
      (node (ref "U2") (pin "25") (pinfunction "SRC_25") (pintype "input"))
    )
    (net (code "61") (name "Net-(U2-STATUS1)") (class "Default")
      (node (ref "U$14") (pin "P$1") (pinfunction "P$1_P$1") (pintype "bidirectional"))
      (node (ref "U2") (pin "20") (pinfunction "STATUS1_20") (pintype "output"))
    )
    (net (code "62") (name "Net-(U2-STATUS2)") (class "Default")
      (node (ref "U$13") (pin "P$1") (pinfunction "P$1_P$1") (pintype "bidirectional"))
      (node (ref "U2") (pin "19") (pinfunction "STATUS2_19") (pintype "output"))
    )
    (net (code "63") (name "Net-(U2-SWBUCK)") (class "Default")
      (node (ref "U$1") (pin "2") (pinfunction "2_2") (pintype "passive"))
      (node (ref "U2") (pin "2") (pinfunction "SWBUCK_2") (pintype "bidirectional"))
    )
    (net (code "64") (name "unconnected-(U$10-P1-Pad1)") (class "Default")
      (node (ref "U$10") (pin "1") (pinfunction "P1_1") (pintype "bidirectional"))
    )
    (net (code "65") (name "unconnected-(U$10-P3-Pad3)") (class "Default")
      (node (ref "U$10") (pin "3") (pinfunction "P3_3") (pintype "bidirectional"))
    )
    (net (code "66") (name "unconnected-(U1-NC-Pad44)") (class "Default")
      (node (ref "U1") (pin "44") (pinfunction "NC_44") (pintype "bidirectional"))
    )
    (net (code "67") (name "unconnected-(U1-P19-Pad22)") (class "Default")
      (node (ref "U1") (pin "22") (pinfunction "P19_22") (pintype "bidirectional"))
    )
    (net (code "68") (name "unconnected-(U1-P20-Pad23)") (class "Default")
      (node (ref "U1") (pin "23") (pinfunction "P20_23") (pintype "bidirectional"))
    )
    (net (code "69") (name "unconnected-(U1-P22-Pad27)") (class "Default")
      (node (ref "U1") (pin "27") (pinfunction "P22_27") (pintype "bidirectional"))
    )
    (net (code "70") (name "unconnected-(U1-P23-Pad28)") (class "Default")
      (node (ref "U1") (pin "28") (pinfunction "P23_28") (pintype "bidirectional"))
    )
    (net (code "71") (name "unconnected-(U1-P24-Pad29)") (class "Default")
      (node (ref "U1") (pin "29") (pinfunction "P24_29") (pintype "bidirectional"))
    )
    (net (code "72") (name "unconnected-(U1-P25-Pad37)") (class "Default")
      (node (ref "U1") (pin "37") (pinfunction "P25_37") (pintype "bidirectional"))
    )
    (net (code "73") (name "unconnected-(U1-P26-Pad38)") (class "Default")
      (node (ref "U1") (pin "38") (pinfunction "P26_38") (pintype "bidirectional"))
    )
    (net (code "74") (name "unconnected-(U1-P27-Pad39)") (class "Default")
      (node (ref "U1") (pin "39") (pinfunction "P27_39") (pintype "bidirectional"))
    )
    (net (code "75") (name "unconnected-(U1-P28-Pad40)") (class "Default")
      (node (ref "U1") (pin "40") (pinfunction "P28_40") (pintype "bidirectional"))
    )
    (net (code "76") (name "unconnected-(U1-P29-Pad41)") (class "Default")
      (node (ref "U1") (pin "41") (pinfunction "P29_41") (pintype "bidirectional"))
    )
    (net (code "77") (name "unconnected-(U1-P30_AIN6-Pad42)") (class "Default")
      (node (ref "U1") (pin "42") (pinfunction "P30_AIN6_42") (pintype "bidirectional"))
    )
    (net (code "78") (name "unconnected-(U1-P31_AIN7-Pad43)") (class "Default")
      (node (ref "U1") (pin "43") (pinfunction "P31_AIN7_43") (pintype "bidirectional"))
    )
  )
)
